# Wheatstone.net
KiCad netlist of a schematic drawn in EAGLE
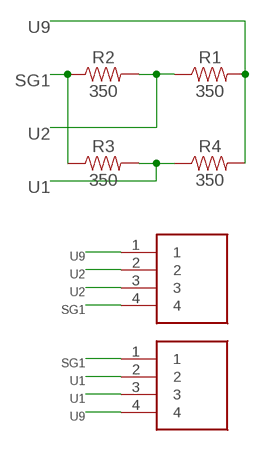
[diagram p0: schematic, sheet 1]

(export (version "E")
  (design (tool "Eeschema 10.0.6"))
  (components
    (comp (ref "J1")
      (value "1725672")
      (footprint "eagle-import:1725672-4-2.54")
      (fields (field (name "RS_PART_NUMBER") "3924476"))
      (libsource (lib "eagle-import") (part "1725672"))
    )
    (comp (ref "J2")
      (value "1725672")
      (footprint "eagle-import:1725672-4-2.54")
      (fields (field (name "RS_PART_NUMBER") "3924476"))
      (libsource (lib "eagle-import") (part "1725672"))
    )
    (comp (ref "R1")
      (value "350")
      (footprint "eagle-import:AXIAL-0.3")
      (libsource (lib "eagle-import") (part "330OHM-HORIZ-1/10W-5%"))
    )
    (comp (ref "R2")
      (value "350")
      (footprint "eagle-import:AXIAL-0.3")
      (libsource (lib "eagle-import") (part "330OHM-HORIZ-1/10W-5%"))
    )
    (comp (ref "R3")
      (value "350")
      (footprint "eagle-import:AXIAL-0.3")
      (libsource (lib "eagle-import") (part "330OHM-HORIZ-1/10W-5%"))
    )
    (comp (ref "R4")
      (value "350")
      (footprint "eagle-import:AXIAL-0.3")
      (libsource (lib "eagle-import") (part "330OHM-HORIZ-1/10W-5%"))
    )
  )
  (nets
    (net (code "1") (name "SG1") (class "Default")
      (node (ref "J1") (pin "4") (pinfunction "4_4") (pintype "bidirectional"))
      (node (ref "J2") (pin "1") (pinfunction "1_1") (pintype "bidirectional"))
      (node (ref "R2") (pin "P$1") (pinfunction "1_P$1") (pintype "passive"))
      (node (ref "R3") (pin "P$1") (pinfunction "1_P$1") (pintype "passive"))
    )
    (net (code "2") (name "U1") (class "Default")
      (node (ref "J2") (pin "2") (pinfunction "2_2") (pintype "bidirectional"))
      (node (ref "J2") (pin "3") (pinfunction "3_3") (pintype "bidirectional"))
      (node (ref "R3") (pin "P$2") (pinfunction "2_P$2") (pintype "passive"))
      (node (ref "R4") (pin "P$1") (pinfunction "1_P$1") (pintype "passive"))
    )
    (net (code "3") (name "U2") (class "Default")
      (node (ref "J1") (pin "2") (pinfunction "2_2") (pintype "bidirectional"))
      (node (ref "J1") (pin "3") (pinfunction "3_3") (pintype "bidirectional"))
      (node (ref "R1") (pin "P$1") (pinfunction "1_P$1") (pintype "passive"))
      (node (ref "R2") (pin "P$2") (pinfunction "2_P$2") (pintype "passive"))
    )
    (net (code "4") (name "U9") (class "Default")
      (node (ref "J1") (pin "1") (pinfunction "1_1") (pintype "bidirectional"))
      (node (ref "J2") (pin "4") (pinfunction "4_4") (pintype "bidirectional"))
      (node (ref "R1") (pin "P$2") (pinfunction "2_P$2") (pintype "passive"))
      (node (ref "R4") (pin "P$2") (pinfunction "2_P$2") (pintype "passive"))
    )
  )
)
